# SimuRain_v2_2_Leonardo.net
KiCad netlist of a schematic drawn in EAGLE
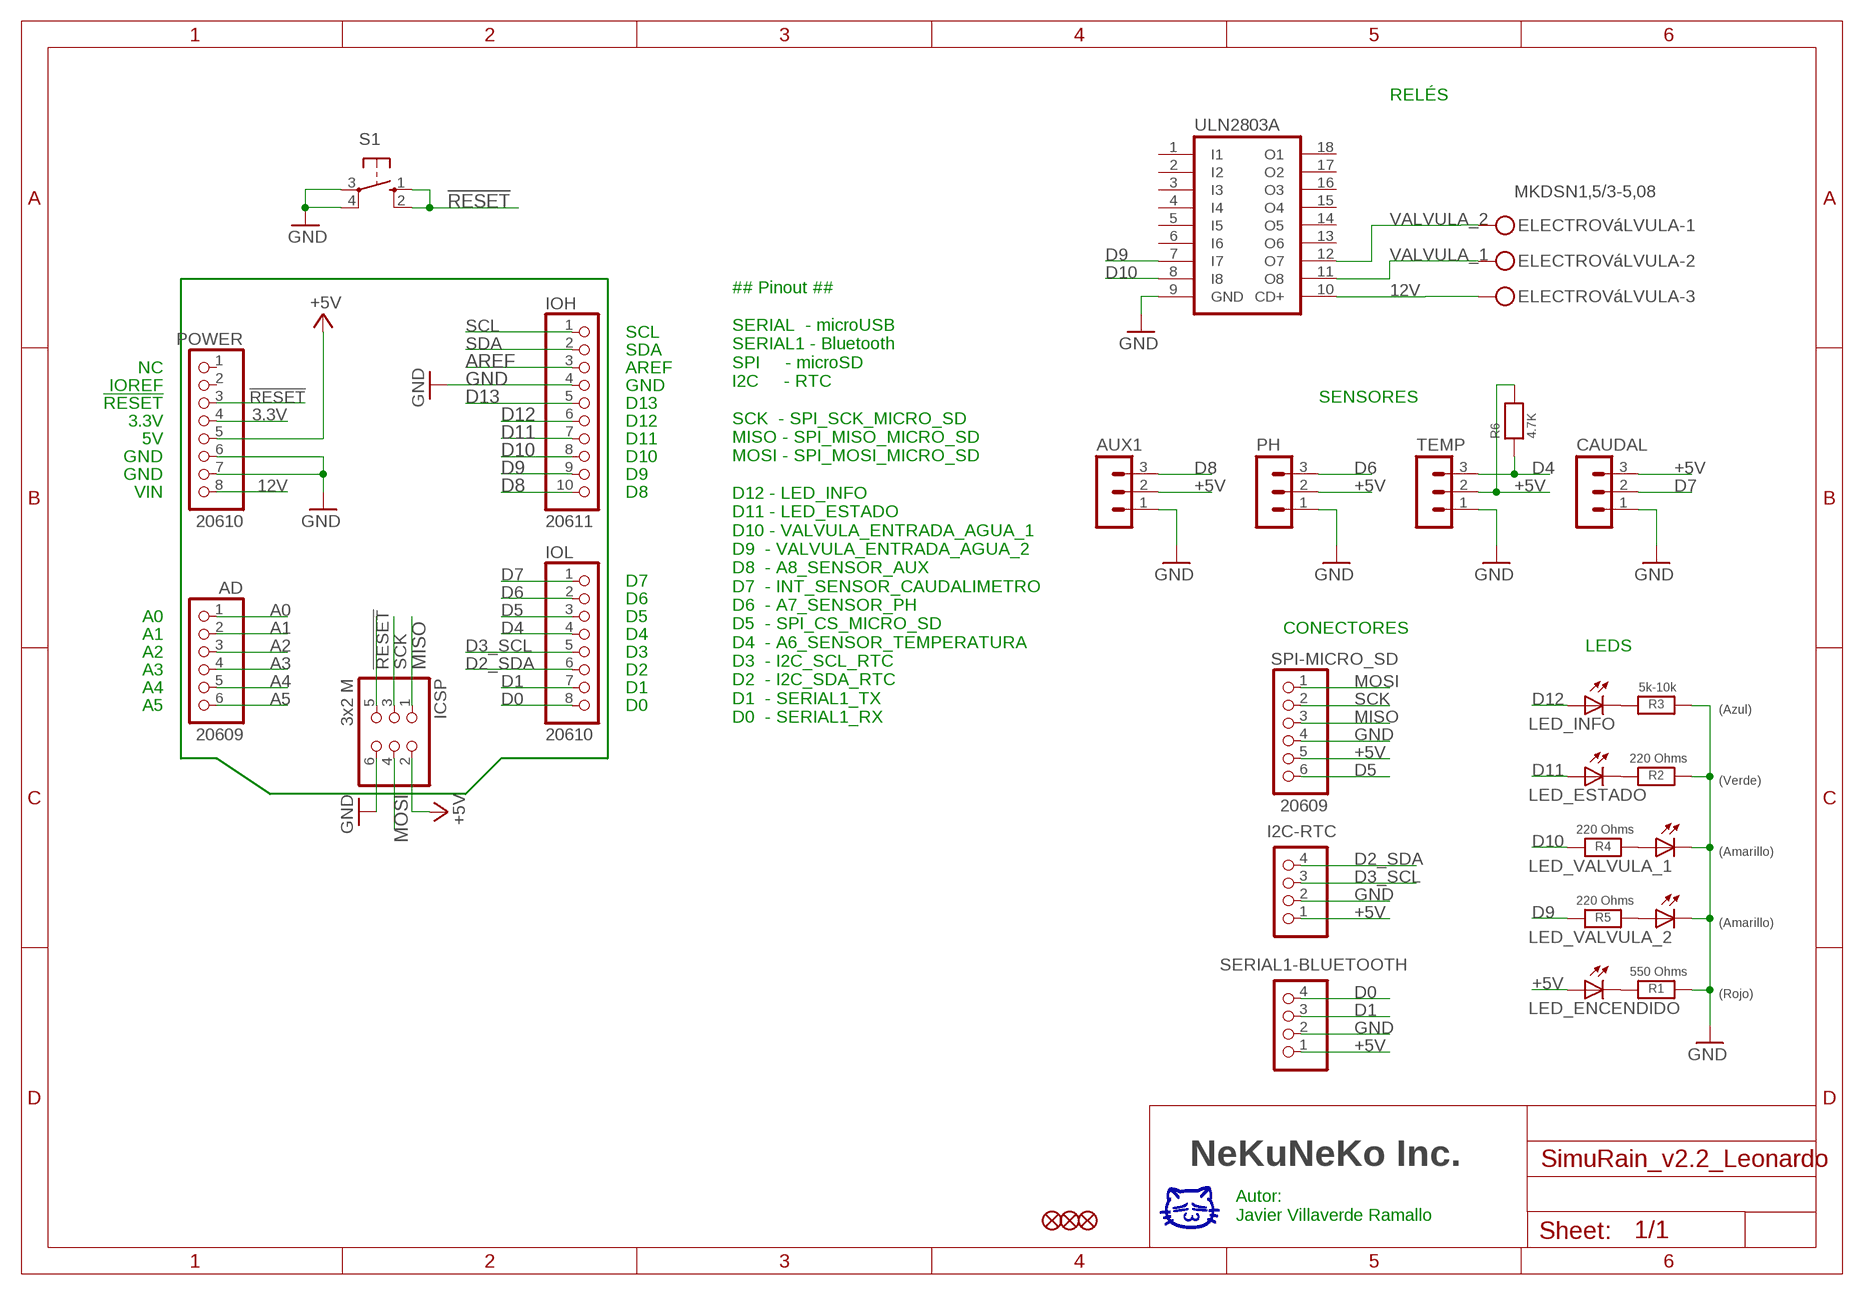
[diagram p0: schematic, sheet 1]

(export (version "E")
  (design (tool "Eeschema 10.0.6"))
  (components
    (comp (ref "AD")
      (value "20609")
      (footprint "eagle-import:1X06_OVALWAVE")
      (libsource (lib "eagle-import") (part "HEADER-1X6OVALWAVE"))
    )
    (comp (ref "AUX1")
      (value "MA03-1")
      (footprint "eagle-import:MA03-1")
      (libsource (lib "eagle-import") (part "MA03-1"))
    )
    (comp (ref "CAUDAL")
      (value "MA03-1")
      (footprint "eagle-import:MA03-1")
      (libsource (lib "eagle-import") (part "MA03-1"))
    )
    (comp (ref "ELECTROVáLVULA")
      (value "MKDSN1,5/3-5,08")
      (footprint "eagle-import:MKDSN1,5_3-5,08")
      (libsource (lib "eagle-import") (part "MKDSN1,5/3-5,08"))
    )
    (comp (ref "FD1")
      (value "FIDUCIAL_1MM")
      (footprint "eagle-import:FIDUCIAL_1MM")
      (libsource (lib "eagle-import") (part "FIDUCIAL_1MM"))
    )
    (comp (ref "FD2")
      (value "FIDUCIAL_1MM")
      (footprint "eagle-import:FIDUCIAL_1MM")
      (libsource (lib "eagle-import") (part "FIDUCIAL_1MM"))
    )
    (comp (ref "FD3")
      (value "FIDUCIAL_1MM")
      (footprint "eagle-import:FIDUCIAL_1MM")
      (libsource (lib "eagle-import") (part "FIDUCIAL_1MM"))
    )
    (comp (ref "I2C-RTC")
      (value "HEADER-1X4")
      (footprint "eagle-import:1X04_OVAL")
      (libsource (lib "eagle-import") (part "HEADER-1X4"))
    )
    (comp (ref "ICSP")
      (value "3x2 M")
      (footprint "eagle-import:2X03_ROUND_70MIL")
      (libsource (lib "eagle-import") (part "HEADER-2X3"))
    )
    (comp (ref "IOH")
      (value "20611")
      (footprint "eagle-import:1X10_OVALWAVE")
      (libsource (lib "eagle-import") (part "HEADER-1X10OVALWAVE"))
    )
    (comp (ref "IOL")
      (value "20610")
      (footprint "eagle-import:1X08_OVALWAVE")
      (libsource (lib "eagle-import") (part "HEADER-1X8OVALWAVE"))
    )
    (comp (ref "LED_ENCENDIDO")
      (value "LED5MM")
      (footprint "eagle-import:LED5MM")
      (libsource (lib "eagle-import") (part "LED5MM"))
    )
    (comp (ref "LED_ESTADO")
      (value "LED5MM")
      (footprint "eagle-import:LED5MM")
      (libsource (lib "eagle-import") (part "LED5MM"))
    )
    (comp (ref "LED_INFO")
      (value "LED5MM")
      (footprint "eagle-import:LED5MM")
      (libsource (lib "eagle-import") (part "LED5MM"))
    )
    (comp (ref "LED_VALVULA_1")
      (value "LED5MM")
      (footprint "eagle-import:LED5MM")
      (libsource (lib "eagle-import") (part "LED5MM"))
    )
    (comp (ref "LED_VALVULA_2")
      (value "LED5MM")
      (footprint "eagle-import:LED5MM")
      (libsource (lib "eagle-import") (part "LED5MM"))
    )
    (comp (ref "PH")
      (value "MA03-1")
      (footprint "eagle-import:MA03-1")
      (libsource (lib "eagle-import") (part "MA03-1"))
    )
    (comp (ref "POWER")
      (value "20610")
      (footprint "eagle-import:1X08_OVALWAVE")
      (libsource (lib "eagle-import") (part "HEADER-1X8OVALWAVE"))
    )
    (comp (ref "R1")
      (value "550 Ohms")
      (footprint "eagle-import:_0805")
      (libsource (lib "eagle-import") (part "RESISTOR_0805"))
    )
    (comp (ref "R2")
      (value "220 Ohms")
      (footprint "eagle-import:_0805")
      (libsource (lib "eagle-import") (part "RESISTOR_0805"))
    )
    (comp (ref "R3")
      (value "5k-10k")
      (footprint "eagle-import:_0805")
      (libsource (lib "eagle-import") (part "RESISTOR_0805"))
    )
    (comp (ref "R4")
      (value "220 Ohms")
      (footprint "eagle-import:_0805")
      (libsource (lib "eagle-import") (part "RESISTOR_0805"))
    )
    (comp (ref "R5")
      (value "220 Ohms")
      (footprint "eagle-import:_0805")
      (libsource (lib "eagle-import") (part "RESISTOR_0805"))
    )
    (comp (ref "R6")
      (value "4.7K")
      (footprint "eagle-import:_0805")
      (libsource (lib "eagle-import") (part "RESISTOR_0805"))
    )
    (comp (ref "S1")
      (value "10-XX")
      (footprint "eagle-import:B3F-10XX")
      (fields (field (name "MPN") "B3F-1000"))
      (libsource (lib "eagle-import") (part "10-XX"))
    )
    (comp (ref "SERIAL1-BLUETOOTH")
      (value "HEADER-1X4")
      (footprint "eagle-import:1X04_OVAL")
      (libsource (lib "eagle-import") (part "HEADER-1X4"))
    )
    (comp (ref "SPI-MICRO_SD")
      (value "20609")
      (footprint "eagle-import:1X06_OVALWAVE")
      (libsource (lib "eagle-import") (part "HEADER-1X6OVALWAVE"))
    )
    (comp (ref "TEMP")
      (value "MA03-1")
      (footprint "eagle-import:MA03-1")
      (libsource (lib "eagle-import") (part "MA03-1"))
    )
    (comp (ref "ULN2803A")
      (value "ULN2803A")
      (footprint "eagle-import:DIL18")
      (libsource (lib "eagle-import") (part "ULN2803A"))
    )
  )
  (nets
    (net (code "1") (name "+5V") (class "Default")
      (node (ref "AUX1") (pin "2") (pinfunction "2_2") (pintype "passive"))
      (node (ref "CAUDAL") (pin "3") (pinfunction "3_3") (pintype "passive"))
      (node (ref "I2C-RTC") (pin "1") (pinfunction "1_1") (pintype "passive"))
      (node (ref "ICSP") (pin "2") (pinfunction "2_2") (pintype "passive"))
      (node (ref "LED_ENCENDIDO") (pin "A") (pinfunction "A_A") (pintype "passive"))
      (node (ref "PH") (pin "2") (pinfunction "2_2") (pintype "passive"))
      (node (ref "POWER") (pin "5") (pinfunction "5_5") (pintype "passive"))
      (node (ref "R6") (pin "2") (pinfunction "2_2") (pintype "passive"))
      (node (ref "SERIAL1-BLUETOOTH") (pin "1") (pinfunction "1_1") (pintype "passive"))
      (node (ref "SPI-MICRO_SD") (pin "5") (pinfunction "5_5") (pintype "passive"))
      (node (ref "TEMP") (pin "2") (pinfunction "2_2") (pintype "passive"))
    )
    (net (code "2") (name "/3.3V") (class "Default")
      (node (ref "POWER") (pin "4") (pinfunction "4_4") (pintype "passive"))
    )
    (net (code "3") (name "/12V") (class "Default")
      (node (ref "ELECTROVáLVULA") (pin "3") (pinfunction "KL_3") (pintype "passive"))
      (node (ref "POWER") (pin "8") (pinfunction "8_8") (pintype "passive"))
      (node (ref "ULN2803A") (pin "10") (pinfunction "CD+_10") (pintype "passive"))
    )
    (net (code "4") (name "/A0") (class "Default")
      (node (ref "AD") (pin "1") (pinfunction "1_1") (pintype "passive"))
    )
    (net (code "5") (name "/A1") (class "Default")
      (node (ref "AD") (pin "2") (pinfunction "2_2") (pintype "passive"))
    )
    (net (code "6") (name "/A2") (class "Default")
      (node (ref "AD") (pin "3") (pinfunction "3_3") (pintype "passive"))
    )
    (net (code "7") (name "/A3") (class "Default")
      (node (ref "AD") (pin "4") (pinfunction "4_4") (pintype "passive"))
    )
    (net (code "8") (name "/A4") (class "Default")
      (node (ref "AD") (pin "5") (pinfunction "5_5") (pintype "passive"))
    )
    (net (code "9") (name "/A5") (class "Default")
      (node (ref "AD") (pin "6") (pinfunction "6_6") (pintype "passive"))
    )
    (net (code "10") (name "/AREF") (class "Default")
      (node (ref "IOH") (pin "3") (pinfunction "3_3") (pintype "passive"))
    )
    (net (code "11") (name "/D0") (class "Default")
      (node (ref "IOL") (pin "8") (pinfunction "8_8") (pintype "passive"))
      (node (ref "SERIAL1-BLUETOOTH") (pin "4") (pinfunction "4_4") (pintype "passive"))
    )
    (net (code "12") (name "/D1") (class "Default")
      (node (ref "IOL") (pin "7") (pinfunction "7_7") (pintype "passive"))
      (node (ref "SERIAL1-BLUETOOTH") (pin "3") (pinfunction "3_3") (pintype "passive"))
    )
    (net (code "13") (name "/D2_SDA") (class "Default")
      (node (ref "I2C-RTC") (pin "4") (pinfunction "4_4") (pintype "passive"))
      (node (ref "IOL") (pin "6") (pinfunction "6_6") (pintype "passive"))
    )
    (net (code "14") (name "/D3_SCL") (class "Default")
      (node (ref "I2C-RTC") (pin "3") (pinfunction "3_3") (pintype "passive"))
      (node (ref "IOL") (pin "5") (pinfunction "5_5") (pintype "passive"))
    )
    (net (code "15") (name "/D4") (class "Default")
      (node (ref "IOL") (pin "4") (pinfunction "4_4") (pintype "passive"))
      (node (ref "R6") (pin "1") (pinfunction "1_1") (pintype "passive"))
      (node (ref "TEMP") (pin "3") (pinfunction "3_3") (pintype "passive"))
    )
    (net (code "16") (name "/D5") (class "Default")
      (node (ref "IOL") (pin "3") (pinfunction "3_3") (pintype "passive"))
      (node (ref "SPI-MICRO_SD") (pin "6") (pinfunction "6_6") (pintype "passive"))
    )
    (net (code "17") (name "/D6") (class "Default")
      (node (ref "IOL") (pin "2") (pinfunction "2_2") (pintype "passive"))
      (node (ref "PH") (pin "3") (pinfunction "3_3") (pintype "passive"))
    )
    (net (code "18") (name "/D7") (class "Default")
      (node (ref "CAUDAL") (pin "2") (pinfunction "2_2") (pintype "passive"))
      (node (ref "IOL") (pin "1") (pinfunction "1_1") (pintype "passive"))
    )
    (net (code "19") (name "/D8") (class "Default")
      (node (ref "AUX1") (pin "3") (pinfunction "3_3") (pintype "passive"))
      (node (ref "IOH") (pin "10") (pinfunction "10_10") (pintype "passive"))
    )
    (net (code "20") (name "/D9") (class "Default")
      (node (ref "IOH") (pin "9") (pinfunction "9_9") (pintype "passive"))
      (node (ref "R5") (pin "1") (pinfunction "1_1") (pintype "passive"))
      (node (ref "ULN2803A") (pin "7") (pinfunction "I7_7") (pintype "input"))
    )
    (net (code "21") (name "/D10") (class "Default")
      (node (ref "IOH") (pin "8") (pinfunction "8_8") (pintype "passive"))
      (node (ref "R4") (pin "1") (pinfunction "1_1") (pintype "passive"))
      (node (ref "ULN2803A") (pin "8") (pinfunction "I8_8") (pintype "input"))
    )
    (net (code "22") (name "/D11") (class "Default")
      (node (ref "IOH") (pin "7") (pinfunction "7_7") (pintype "passive"))
      (node (ref "LED_ESTADO") (pin "A") (pinfunction "A_A") (pintype "passive"))
    )
    (net (code "23") (name "/D12") (class "Default")
      (node (ref "IOH") (pin "6") (pinfunction "6_6") (pintype "passive"))
      (node (ref "LED_INFO") (pin "A") (pinfunction "A_A") (pintype "passive"))
    )
    (net (code "24") (name "/D13") (class "Default")
      (node (ref "IOH") (pin "5") (pinfunction "5_5") (pintype "passive"))
    )
    (net (code "25") (name "/MISO") (class "Default")
      (node (ref "ICSP") (pin "1") (pinfunction "1_1") (pintype "passive"))
      (node (ref "SPI-MICRO_SD") (pin "3") (pinfunction "3_3") (pintype "passive"))
    )
    (net (code "26") (name "/MOSI") (class "Default")
      (node (ref "ICSP") (pin "4") (pinfunction "4_4") (pintype "passive"))
      (node (ref "SPI-MICRO_SD") (pin "1") (pinfunction "1_1") (pintype "passive"))
    )
    (net (code "27") (name "/SCK") (class "Default")
      (node (ref "ICSP") (pin "3") (pinfunction "3_3") (pintype "passive"))
      (node (ref "SPI-MICRO_SD") (pin "2") (pinfunction "2_2") (pintype "passive"))
    )
    (net (code "28") (name "/SCL") (class "Default")
      (node (ref "IOH") (pin "1") (pinfunction "1_1") (pintype "passive"))
    )
    (net (code "29") (name "/SDA") (class "Default")
      (node (ref "IOH") (pin "2") (pinfunction "2_2") (pintype "passive"))
    )
    (net (code "30") (name "/VALVULA_1") (class "Default")
      (node (ref "ELECTROVáLVULA") (pin "2") (pinfunction "KL_2") (pintype "passive"))
      (node (ref "ULN2803A") (pin "11") (pinfunction "O8_11") (pintype "open_collector"))
    )
    (net (code "31") (name "/VALVULA_2") (class "Default")
      (node (ref "ELECTROVáLVULA") (pin "1") (pinfunction "KL_1") (pintype "passive"))
      (node (ref "ULN2803A") (pin "12") (pinfunction "O7_12") (pintype "open_collector"))
    )
    (net (code "32") (name "/~{RESET}") (class "Default")
      (node (ref "ICSP") (pin "5") (pinfunction "5_5") (pintype "passive"))
      (node (ref "POWER") (pin "3") (pinfunction "3_3") (pintype "passive"))
      (node (ref "S1") (pin "1") (pinfunction "S_1") (pintype "passive"))
      (node (ref "S1") (pin "2") (pinfunction "S1_2") (pintype "passive"))
    )
    (net (code "33") (name "GND") (class "Default")
      (node (ref "AUX1") (pin "1") (pinfunction "1_1") (pintype "passive"))
      (node (ref "CAUDAL") (pin "1") (pinfunction "1_1") (pintype "passive"))
      (node (ref "I2C-RTC") (pin "2") (pinfunction "2_2") (pintype "passive"))
      (node (ref "ICSP") (pin "6") (pinfunction "6_6") (pintype "passive"))
      (node (ref "IOH") (pin "4") (pinfunction "4_4") (pintype "passive"))
      (node (ref "LED_VALVULA_1") (pin "K") (pinfunction "C_K") (pintype "passive"))
      (node (ref "LED_VALVULA_2") (pin "K") (pinfunction "C_K") (pintype "passive"))
      (node (ref "PH") (pin "1") (pinfunction "1_1") (pintype "passive"))
      (node (ref "POWER") (pin "6") (pinfunction "6_6") (pintype "passive"))
      (node (ref "POWER") (pin "7") (pinfunction "7_7") (pintype "passive"))
      (node (ref "R1") (pin "2") (pinfunction "2_2") (pintype "passive"))
      (node (ref "R2") (pin "2") (pinfunction "2_2") (pintype "passive"))
      (node (ref "R3") (pin "2") (pinfunction "2_2") (pintype "passive"))
      (node (ref "S1") (pin "3") (pinfunction "P_3") (pintype "passive"))
      (node (ref "S1") (pin "4") (pinfunction "P1_4") (pintype "passive"))
      (node (ref "SERIAL1-BLUETOOTH") (pin "2") (pinfunction "2_2") (pintype "passive"))
      (node (ref "SPI-MICRO_SD") (pin "4") (pinfunction "4_4") (pintype "passive"))
      (node (ref "TEMP") (pin "1") (pinfunction "1_1") (pintype "passive"))
      (node (ref "ULN2803A") (pin "9") (pinfunction "GND_9") (pintype "power_in"))
    )
    (net (code "34") (name "Net-(LED_ENCENDIDO-C)") (class "Default")
      (node (ref "LED_ENCENDIDO") (pin "K") (pinfunction "C_K") (pintype "passive"))
      (node (ref "R1") (pin "1") (pinfunction "1_1") (pintype "passive"))
    )
    (net (code "35") (name "Net-(LED_ESTADO-C)") (class "Default")
      (node (ref "LED_ESTADO") (pin "K") (pinfunction "C_K") (pintype "passive"))
      (node (ref "R2") (pin "1") (pinfunction "1_1") (pintype "passive"))
    )
    (net (code "36") (name "Net-(LED_INFO-C)") (class "Default")
      (node (ref "LED_INFO") (pin "K") (pinfunction "C_K") (pintype "passive"))
      (node (ref "R3") (pin "1") (pinfunction "1_1") (pintype "passive"))
    )
    (net (code "37") (name "Net-(LED_VALVULA_1-PadA)") (class "Default")
      (node (ref "LED_VALVULA_1") (pin "A") (pinfunction "A_A") (pintype "passive"))
      (node (ref "R4") (pin "2") (pinfunction "2_2") (pintype "passive"))
    )
    (net (code "38") (name "Net-(LED_VALVULA_2-PadA)") (class "Default")
      (node (ref "LED_VALVULA_2") (pin "A") (pinfunction "A_A") (pintype "passive"))
      (node (ref "R5") (pin "2") (pinfunction "2_2") (pintype "passive"))
    )
    (net (code "39") (name "unconnected-(POWER-Pad1)") (class "Default")
      (node (ref "POWER") (pin "1") (pinfunction "1_1") (pintype "passive"))
    )
    (net (code "40") (name "unconnected-(POWER-Pad2)") (class "Default")
      (node (ref "POWER") (pin "2") (pinfunction "2_2") (pintype "passive"))
    )
    (net (code "41") (name "unconnected-(ULN2803A-I1-Pad1)") (class "Default")
      (node (ref "ULN2803A") (pin "1") (pinfunction "I1_1") (pintype "input"))
    )
    (net (code "42") (name "unconnected-(ULN2803A-I2-Pad2)") (class "Default")
      (node (ref "ULN2803A") (pin "2") (pinfunction "I2_2") (pintype "input"))
    )
    (net (code "43") (name "unconnected-(ULN2803A-I3-Pad3)") (class "Default")
      (node (ref "ULN2803A") (pin "3") (pinfunction "I3_3") (pintype "input"))
    )
    (net (code "44") (name "unconnected-(ULN2803A-I4-Pad4)") (class "Default")
      (node (ref "ULN2803A") (pin "4") (pinfunction "I4_4") (pintype "input"))
    )
    (net (code "45") (name "unconnected-(ULN2803A-I5-Pad5)") (class "Default")
      (node (ref "ULN2803A") (pin "5") (pinfunction "I5_5") (pintype "input"))
    )
    (net (code "46") (name "unconnected-(ULN2803A-I6-Pad6)") (class "Default")
      (node (ref "ULN2803A") (pin "6") (pinfunction "I6_6") (pintype "input"))
    )
    (net (code "47") (name "unconnected-(ULN2803A-O1-Pad18)") (class "Default")
      (node (ref "ULN2803A") (pin "18") (pinfunction "O1_18") (pintype "open_collector"))
    )
    (net (code "48") (name "unconnected-(ULN2803A-O2-Pad17)") (class "Default")
      (node (ref "ULN2803A") (pin "17") (pinfunction "O2_17") (pintype "open_collector"))
    )
    (net (code "49") (name "unconnected-(ULN2803A-O3-Pad16)") (class "Default")
      (node (ref "ULN2803A") (pin "16") (pinfunction "O3_16") (pintype "open_collector"))
    )
    (net (code "50") (name "unconnected-(ULN2803A-O4-Pad15)") (class "Default")
      (node (ref "ULN2803A") (pin "15") (pinfunction "O4_15") (pintype "open_collector"))
    )
    (net (code "51") (name "unconnected-(ULN2803A-O5-Pad14)") (class "Default")
      (node (ref "ULN2803A") (pin "14") (pinfunction "O5_14") (pintype "open_collector"))
    )
    (net (code "52") (name "unconnected-(ULN2803A-O6-Pad13)") (class "Default")
      (node (ref "ULN2803A") (pin "13") (pinfunction "O6_13") (pintype "open_collector"))
    )
  )
)
